# power_1_0.net
KiCad netlist of a schematic drawn in EAGLE
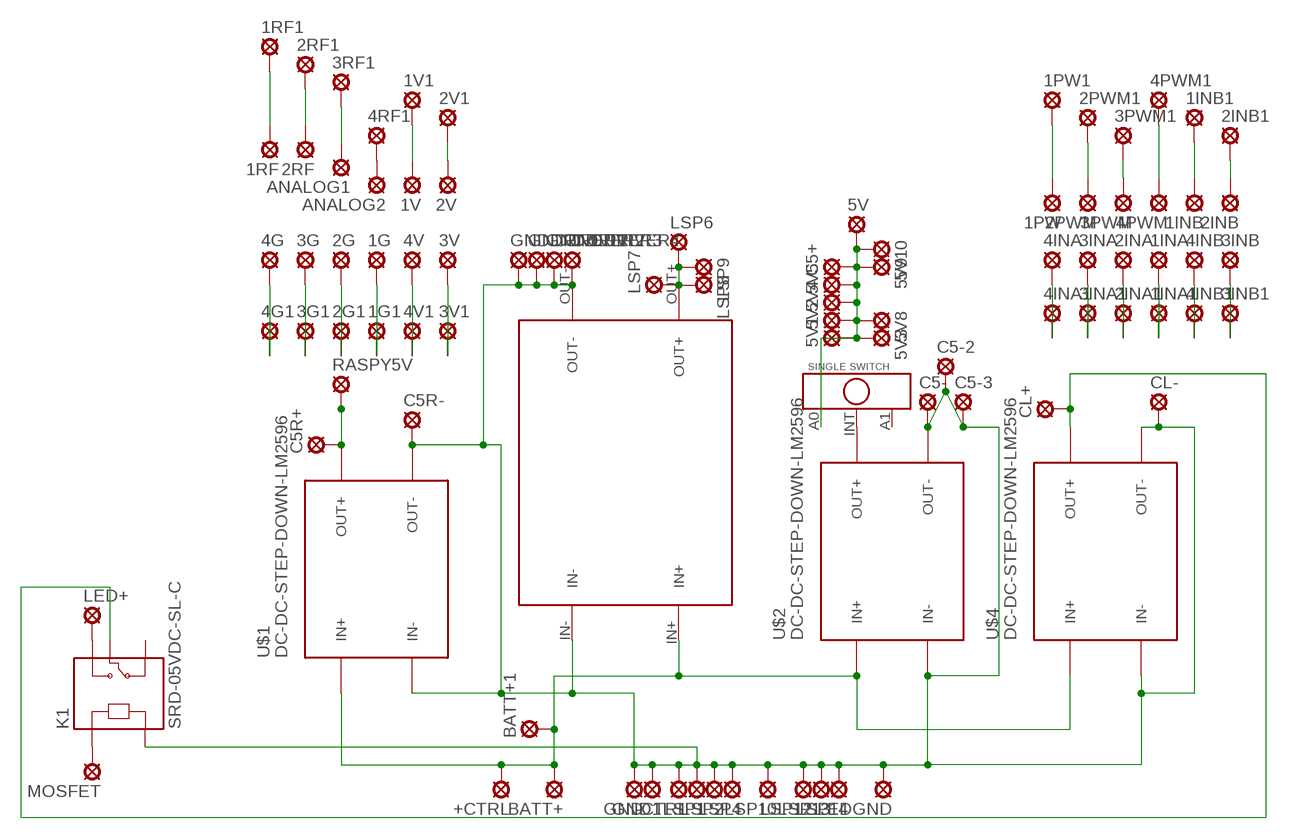
[diagram p0: schematic, sheet 1]

(export (version "E")
  (design (tool "Eeschema 10.0.6"))
  (components
    (comp (ref "+CTRL")
      (value "LSP10")
      (footprint "eagle-import:LSP10")
      (libsource (lib "eagle-import") (part "LSP10"))
    )
    (comp (ref "-CTRL")
      (value "LSP10")
      (footprint "eagle-import:LSP10")
      (libsource (lib "eagle-import") (part "LSP10"))
    )
    (comp (ref "1G")
      (value "LSP10")
      (footprint "eagle-import:LSP10")
      (libsource (lib "eagle-import") (part "LSP10"))
    )
    (comp (ref "1G1")
      (value "LSP10")
      (footprint "eagle-import:LSP10")
      (libsource (lib "eagle-import") (part "LSP10"))
    )
    (comp (ref "1INA")
      (value "LSP10")
      (footprint "eagle-import:LSP10")
      (libsource (lib "eagle-import") (part "LSP10"))
    )
    (comp (ref "1INA1")
      (value "LSP10")
      (footprint "eagle-import:LSP10")
      (libsource (lib "eagle-import") (part "LSP10"))
    )
    (comp (ref "1INB")
      (value "LSP10")
      (footprint "eagle-import:LSP10")
      (libsource (lib "eagle-import") (part "LSP10"))
    )
    (comp (ref "1INB1")
      (value "LSP10")
      (footprint "eagle-import:LSP10")
      (libsource (lib "eagle-import") (part "LSP10"))
    )
    (comp (ref "1PW")
      (value "LSP10")
      (footprint "eagle-import:LSP10")
      (libsource (lib "eagle-import") (part "LSP10"))
    )
    (comp (ref "1PW1")
      (value "LSP10")
      (footprint "eagle-import:LSP10")
      (libsource (lib "eagle-import") (part "LSP10"))
    )
    (comp (ref "1RF")
      (value "LSP10")
      (footprint "eagle-import:LSP10")
      (libsource (lib "eagle-import") (part "LSP10"))
    )
    (comp (ref "1RF1")
      (value "LSP10")
      (footprint "eagle-import:LSP10")
      (libsource (lib "eagle-import") (part "LSP10"))
    )
    (comp (ref "1V")
      (value "LSP10")
      (footprint "eagle-import:LSP10")
      (libsource (lib "eagle-import") (part "LSP10"))
    )
    (comp (ref "1V1")
      (value "LSP10")
      (footprint "eagle-import:LSP10")
      (libsource (lib "eagle-import") (part "LSP10"))
    )
    (comp (ref "2G")
      (value "LSP10")
      (footprint "eagle-import:LSP10")
      (libsource (lib "eagle-import") (part "LSP10"))
    )
    (comp (ref "2G1")
      (value "LSP10")
      (footprint "eagle-import:LSP10")
      (libsource (lib "eagle-import") (part "LSP10"))
    )
    (comp (ref "2INA")
      (value "LSP10")
      (footprint "eagle-import:LSP10")
      (libsource (lib "eagle-import") (part "LSP10"))
    )
    (comp (ref "2INA1")
      (value "LSP10")
      (footprint "eagle-import:LSP10")
      (libsource (lib "eagle-import") (part "LSP10"))
    )
    (comp (ref "2INB")
      (value "LSP10")
      (footprint "eagle-import:LSP10")
      (libsource (lib "eagle-import") (part "LSP10"))
    )
    (comp (ref "2INB1")
      (value "LSP10")
      (footprint "eagle-import:LSP10")
      (libsource (lib "eagle-import") (part "LSP10"))
    )
    (comp (ref "2PWM")
      (value "LSP10")
      (footprint "eagle-import:LSP10")
      (libsource (lib "eagle-import") (part "LSP10"))
    )
    (comp (ref "2PWM1")
      (value "LSP10")
      (footprint "eagle-import:LSP10")
      (libsource (lib "eagle-import") (part "LSP10"))
    )
    (comp (ref "2RF")
      (value "LSP10")
      (footprint "eagle-import:LSP10")
      (libsource (lib "eagle-import") (part "LSP10"))
    )
    (comp (ref "2RF1")
      (value "LSP10")
      (footprint "eagle-import:LSP10")
      (libsource (lib "eagle-import") (part "LSP10"))
    )
    (comp (ref "2V")
      (value "LSP10")
      (footprint "eagle-import:LSP10")
      (libsource (lib "eagle-import") (part "LSP10"))
    )
    (comp (ref "2V1")
      (value "LSP10")
      (footprint "eagle-import:LSP10")
      (libsource (lib "eagle-import") (part "LSP10"))
    )
    (comp (ref "3G")
      (value "LSP10")
      (footprint "eagle-import:LSP10")
      (libsource (lib "eagle-import") (part "LSP10"))
    )
    (comp (ref "3G1")
      (value "LSP10")
      (footprint "eagle-import:LSP10")
      (libsource (lib "eagle-import") (part "LSP10"))
    )
    (comp (ref "3INA")
      (value "LSP10")
      (footprint "eagle-import:LSP10")
      (libsource (lib "eagle-import") (part "LSP10"))
    )
    (comp (ref "3INA1")
      (value "LSP10")
      (footprint "eagle-import:LSP10")
      (libsource (lib "eagle-import") (part "LSP10"))
    )
    (comp (ref "3INB")
      (value "LSP10")
      (footprint "eagle-import:LSP10")
      (libsource (lib "eagle-import") (part "LSP10"))
    )
    (comp (ref "3INB1")
      (value "LSP10")
      (footprint "eagle-import:LSP10")
      (libsource (lib "eagle-import") (part "LSP10"))
    )
    (comp (ref "3PWM")
      (value "LSP10")
      (footprint "eagle-import:LSP10")
      (libsource (lib "eagle-import") (part "LSP10"))
    )
    (comp (ref "3PWM1")
      (value "LSP10")
      (footprint "eagle-import:LSP10")
      (libsource (lib "eagle-import") (part "LSP10"))
    )
    (comp (ref "3RF1")
      (value "LSP10")
      (footprint "eagle-import:LSP10")
      (libsource (lib "eagle-import") (part "LSP10"))
    )
    (comp (ref "3V")
      (value "LSP10")
      (footprint "eagle-import:LSP10")
      (libsource (lib "eagle-import") (part "LSP10"))
    )
    (comp (ref "3V1")
      (value "LSP10")
      (footprint "eagle-import:LSP10")
      (libsource (lib "eagle-import") (part "LSP10"))
    )
    (comp (ref "4G")
      (value "LSP10")
      (footprint "eagle-import:LSP10")
      (libsource (lib "eagle-import") (part "LSP10"))
    )
    (comp (ref "4G1")
      (value "LSP10")
      (footprint "eagle-import:LSP10")
      (libsource (lib "eagle-import") (part "LSP10"))
    )
    (comp (ref "4INA")
      (value "LSP10")
      (footprint "eagle-import:LSP10")
      (libsource (lib "eagle-import") (part "LSP10"))
    )
    (comp (ref "4INA1")
      (value "LSP10")
      (footprint "eagle-import:LSP10")
      (libsource (lib "eagle-import") (part "LSP10"))
    )
    (comp (ref "4INB")
      (value "LSP10")
      (footprint "eagle-import:LSP10")
      (libsource (lib "eagle-import") (part "LSP10"))
    )
    (comp (ref "4INB1")
      (value "LSP10")
      (footprint "eagle-import:LSP10")
      (libsource (lib "eagle-import") (part "LSP10"))
    )
    (comp (ref "4PWM")
      (value "LSP10")
      (footprint "eagle-import:LSP10")
      (libsource (lib "eagle-import") (part "LSP10"))
    )
    (comp (ref "4PWM1")
      (value "LSP10")
      (footprint "eagle-import:LSP10")
      (libsource (lib "eagle-import") (part "LSP10"))
    )
    (comp (ref "4RF1")
      (value "LSP10")
      (footprint "eagle-import:LSP10")
      (libsource (lib "eagle-import") (part "LSP10"))
    )
    (comp (ref "4V")
      (value "LSP10")
      (footprint "eagle-import:LSP10")
      (libsource (lib "eagle-import") (part "LSP10"))
    )
    (comp (ref "4V1")
      (value "LSP10")
      (footprint "eagle-import:LSP10")
      (libsource (lib "eagle-import") (part "LSP10"))
    )
    (comp (ref "5V")
      (value "LSP10")
      (footprint "eagle-import:LSP10")
      (libsource (lib "eagle-import") (part "LSP10"))
    )
    (comp (ref "5V1")
      (value "LSP10")
      (footprint "eagle-import:LSP10")
      (libsource (lib "eagle-import") (part "LSP10"))
    )
    (comp (ref "5V2")
      (value "LSP10")
      (footprint "eagle-import:LSP10")
      (libsource (lib "eagle-import") (part "LSP10"))
    )
    (comp (ref "5V3")
      (value "LSP10")
      (footprint "eagle-import:LSP10")
      (libsource (lib "eagle-import") (part "LSP10"))
    )
    (comp (ref "5V4")
      (value "LSP10")
      (footprint "eagle-import:LSP10")
      (libsource (lib "eagle-import") (part "LSP10"))
    )
    (comp (ref "5V5")
      (value "LSP10")
      (footprint "eagle-import:LSP10")
      (libsource (lib "eagle-import") (part "LSP10"))
    )
    (comp (ref "5V8")
      (value "LSP10")
      (footprint "eagle-import:LSP10")
      (libsource (lib "eagle-import") (part "LSP10"))
    )
    (comp (ref "5V9")
      (value "LSP10")
      (footprint "eagle-import:LSP10")
      (libsource (lib "eagle-import") (part "LSP10"))
    )
    (comp (ref "5V10")
      (value "LSP10")
      (footprint "eagle-import:LSP10")
      (libsource (lib "eagle-import") (part "LSP10"))
    )
    (comp (ref "ANALOG1")
      (value "LSP10")
      (footprint "eagle-import:LSP10")
      (libsource (lib "eagle-import") (part "LSP10"))
    )
    (comp (ref "ANALOG2")
      (value "LSP10")
      (footprint "eagle-import:LSP10")
      (libsource (lib "eagle-import") (part "LSP10"))
    )
    (comp (ref "BATT+")
      (value "SE14")
      (footprint "eagle-import:SE14")
      (libsource (lib "eagle-import") (part "SE14"))
    )
    (comp (ref "BATT+1")
      (value "SE14")
      (footprint "eagle-import:SE14")
      (libsource (lib "eagle-import") (part "SE14"))
    )
    (comp (ref "C5+")
      (value "LSP10")
      (footprint "eagle-import:LSP10")
      (libsource (lib "eagle-import") (part "LSP10"))
    )
    (comp (ref "C5-")
      (value "LSP10")
      (footprint "eagle-import:LSP10")
      (libsource (lib "eagle-import") (part "LSP10"))
    )
    (comp (ref "C5-2")
      (value "LSP10")
      (footprint "eagle-import:LSP10")
      (libsource (lib "eagle-import") (part "LSP10"))
    )
    (comp (ref "C5-3")
      (value "LSP10")
      (footprint "eagle-import:LSP10")
      (libsource (lib "eagle-import") (part "LSP10"))
    )
    (comp (ref "C5R+")
      (value "LSP10")
      (footprint "eagle-import:LSP10")
      (libsource (lib "eagle-import") (part "LSP10"))
    )
    (comp (ref "C5R-")
      (value "LSP10")
      (footprint "eagle-import:LSP10")
      (libsource (lib "eagle-import") (part "LSP10"))
    )
    (comp (ref "CL+")
      (value "LSP10")
      (footprint "eagle-import:LSP10")
      (libsource (lib "eagle-import") (part "LSP10"))
    )
    (comp (ref "CL-")
      (value "LSP10")
      (footprint "eagle-import:LSP10")
      (libsource (lib "eagle-import") (part "LSP10"))
    )
    (comp (ref "GND")
      (value "SE14")
      (footprint "eagle-import:SE14")
      (libsource (lib "eagle-import") (part "SE14"))
    )
    (comp (ref "GND1")
      (value "SE14")
      (footprint "eagle-import:SE14")
      (libsource (lib "eagle-import") (part "SE14"))
    )
    (comp (ref "GNDDRIVER1")
      (value "SE14")
      (footprint "eagle-import:SE14")
      (libsource (lib "eagle-import") (part "SE14"))
    )
    (comp (ref "GNDDRIVER2")
      (value "SE14")
      (footprint "eagle-import:SE14")
      (libsource (lib "eagle-import") (part "SE14"))
    )
    (comp (ref "GNDDRIVER3")
      (value "SE14")
      (footprint "eagle-import:SE14")
      (libsource (lib "eagle-import") (part "SE14"))
    )
    (comp (ref "GNDDRIVER4")
      (value "SE14")
      (footprint "eagle-import:SE14")
      (libsource (lib "eagle-import") (part "SE14"))
    )
    (comp (ref "K1")
      (value "SRD-05VDC-SL-C")
      (footprint "eagle-import:RELAY_SRD-05VDC-SL-C")
      (fields (field (name "MF") "Songle Relay"))
      (libsource (lib "eagle-import") (part "SRD-05VDC-SL-C"))
    )
    (comp (ref "LED+")
      (value "SE14")
      (footprint "eagle-import:SE14")
      (libsource (lib "eagle-import") (part "SE14"))
    )
    (comp (ref "LEDGND")
      (value "SE14")
      (footprint "eagle-import:SE14")
      (libsource (lib "eagle-import") (part "SE14"))
    )
    (comp (ref "LSP1")
      (value "LSP10")
      (footprint "eagle-import:LSP10")
      (libsource (lib "eagle-import") (part "LSP10"))
    )
    (comp (ref "LSP2")
      (value "LSP10")
      (footprint "eagle-import:LSP10")
      (libsource (lib "eagle-import") (part "LSP10"))
    )
    (comp (ref "LSP4")
      (value "LSP10")
      (footprint "eagle-import:LSP10")
      (libsource (lib "eagle-import") (part "LSP10"))
    )
    (comp (ref "LSP6")
      (value "SE14")
      (footprint "eagle-import:SE14")
      (libsource (lib "eagle-import") (part "SE14"))
    )
    (comp (ref "LSP7")
      (value "SE14")
      (footprint "eagle-import:SE14")
      (libsource (lib "eagle-import") (part "SE14"))
    )
    (comp (ref "LSP8")
      (value "SE14")
      (footprint "eagle-import:SE14")
      (libsource (lib "eagle-import") (part "SE14"))
    )
    (comp (ref "LSP9")
      (value "SE14")
      (footprint "eagle-import:SE14")
      (libsource (lib "eagle-import") (part "SE14"))
    )
    (comp (ref "LSP10")
      (value "LSP10")
      (footprint "eagle-import:LSP10")
      (libsource (lib "eagle-import") (part "LSP10"))
    )
    (comp (ref "LSP12")
      (value "LSP10")
      (footprint "eagle-import:LSP10")
      (libsource (lib "eagle-import") (part "LSP10"))
    )
    (comp (ref "LSP13")
      (value "LSP10")
      (footprint "eagle-import:LSP10")
      (libsource (lib "eagle-import") (part "LSP10"))
    )
    (comp (ref "LSP14")
      (value "LSP10")
      (footprint "eagle-import:LSP10")
      (libsource (lib "eagle-import") (part "LSP10"))
    )
    (comp (ref "MOSFET")
      (value "LSP10")
      (footprint "eagle-import:LSP10")
      (libsource (lib "eagle-import") (part "LSP10"))
    )
    (comp (ref "RASPY5V")
      (value "LSP10")
      (footprint "eagle-import:LSP10")
      (libsource (lib "eagle-import") (part "LSP10"))
    )
    (comp (ref "U$1")
      (value "DC-DC-STEP-DOWN-LM2596")
      (footprint "eagle-import:DC-DC-STEP-DOWN-LM2596")
      (libsource (lib "eagle-import") (part "DC-DC-STEP-DOWN-LM2596"))
    )
    (comp (ref "U$2")
      (value "DC-DC-STEP-DOWN-LM2596")
      (footprint "eagle-import:DC-DC-STEP-DOWN-LM2596")
      (libsource (lib "eagle-import") (part "DC-DC-STEP-DOWN-LM2596"))
    )
    (comp (ref "U$3")
      (value "DC-DCSTEPUP/DOWNBUCKCONVERTER")
      (footprint "eagle-import:DC-DCSTEPUP_DOWNBUCKCONVERTER")
      (libsource (lib "eagle-import") (part "DC-DCSTEPUP/DOWNBUCKCONVERTER"))
    )
    (comp (ref "U$4")
      (value "DC-DC-STEP-DOWN-LM2596")
      (footprint "eagle-import:DC-DC-STEP-DOWN-LM2596")
      (libsource (lib "eagle-import") (part "DC-DC-STEP-DOWN-LM2596"))
    )
    (comp (ref "U$5")
      (value "SINGE_SWITCH")
      (footprint "eagle-import:SINGLE_SWITCH")
      (libsource (lib "eagle-import") (part "SINGE_SWITCH"))
    )
  )
  (nets
    (net (code "1") (name "Net-(+CTRL-PadMP)") (class "Default")
      (node (ref "+CTRL") (pin "MP") (pinfunction "MP_MP") (pintype "passive"))
      (node (ref "BATT+") (pin "MP") (pinfunction "MP_MP") (pintype "passive"))
      (node (ref "BATT+1") (pin "MP") (pinfunction "MP_MP") (pintype "passive"))
      (node (ref "U$1") (pin "IN+") (pinfunction "IN+_IN+") (pintype "bidirectional"))
      (node (ref "U$2") (pin "IN+") (pinfunction "IN+_IN+") (pintype "bidirectional"))
      (node (ref "U$3") (pin "IN+") (pinfunction "IN+_IN+") (pintype "bidirectional"))
      (node (ref "U$4") (pin "IN+") (pinfunction "IN+_IN+") (pintype "bidirectional"))
    )
    (net (code "2") (name "Net-(-CTRL-PadMP)") (class "Default")
      (node (ref "-CTRL") (pin "MP") (pinfunction "MP_MP") (pintype "passive"))
      (node (ref "C5-") (pin "MP") (pinfunction "MP_MP") (pintype "passive"))
      (node (ref "C5-2") (pin "MP") (pinfunction "MP_MP") (pintype "passive"))
      (node (ref "C5-3") (pin "MP") (pinfunction "MP_MP") (pintype "passive"))
      (node (ref "C5R-") (pin "MP") (pinfunction "MP_MP") (pintype "passive"))
      (node (ref "CL-") (pin "MP") (pinfunction "MP_MP") (pintype "passive"))
      (node (ref "GND") (pin "MP") (pinfunction "MP_MP") (pintype "passive"))
      (node (ref "GND1") (pin "MP") (pinfunction "MP_MP") (pintype "passive"))
      (node (ref "GNDDRIVER1") (pin "MP") (pinfunction "MP_MP") (pintype "passive"))
      (node (ref "GNDDRIVER2") (pin "MP") (pinfunction "MP_MP") (pintype "passive"))
      (node (ref "GNDDRIVER3") (pin "MP") (pinfunction "MP_MP") (pintype "passive"))
      (node (ref "GNDDRIVER4") (pin "MP") (pinfunction "MP_MP") (pintype "passive"))
      (node (ref "K1") (pin "A2") (pinfunction "A2_A2") (pintype "passive"))
      (node (ref "LEDGND") (pin "MP") (pinfunction "MP_MP") (pintype "passive"))
      (node (ref "LSP1") (pin "MP") (pinfunction "MP_MP") (pintype "passive"))
      (node (ref "LSP10") (pin "MP") (pinfunction "MP_MP") (pintype "passive"))
      (node (ref "LSP12") (pin "MP") (pinfunction "MP_MP") (pintype "passive"))
      (node (ref "LSP13") (pin "MP") (pinfunction "MP_MP") (pintype "passive"))
      (node (ref "LSP14") (pin "MP") (pinfunction "MP_MP") (pintype "passive"))
      (node (ref "LSP2") (pin "MP") (pinfunction "MP_MP") (pintype "passive"))
      (node (ref "LSP4") (pin "MP") (pinfunction "MP_MP") (pintype "passive"))
      (node (ref "U$1") (pin "IN-") (pinfunction "IN-_IN-") (pintype "bidirectional"))
      (node (ref "U$1") (pin "OUT-") (pinfunction "OUT-_OUT-") (pintype "bidirectional"))
      (node (ref "U$2") (pin "IN-") (pinfunction "IN-_IN-") (pintype "bidirectional"))
      (node (ref "U$2") (pin "OUT-") (pinfunction "OUT-_OUT-") (pintype "bidirectional"))
      (node (ref "U$3") (pin "IN-") (pinfunction "IN-_IN-") (pintype "bidirectional"))
      (node (ref "U$3") (pin "OUT-") (pinfunction "OUT-_OUT-") (pintype "bidirectional"))
      (node (ref "U$4") (pin "IN-") (pinfunction "IN-_IN-") (pintype "bidirectional"))
      (node (ref "U$4") (pin "OUT-") (pinfunction "OUT-_OUT-") (pintype "bidirectional"))
    )
    (net (code "3") (name "Net-(1G-PadMP)") (class "Default")
      (node (ref "1G") (pin "MP") (pinfunction "MP_MP") (pintype "passive"))
      (node (ref "1G1") (pin "MP") (pinfunction "MP_MP") (pintype "passive"))
    )
    (net (code "4") (name "Net-(1INA-PadMP)") (class "Default")
      (node (ref "1INA") (pin "MP") (pinfunction "MP_MP") (pintype "passive"))
      (node (ref "1INA1") (pin "MP") (pinfunction "MP_MP") (pintype "passive"))
    )
    (net (code "5") (name "Net-(1INB-PadMP)") (class "Default")
      (node (ref "1INB") (pin "MP") (pinfunction "MP_MP") (pintype "passive"))
      (node (ref "1INB1") (pin "MP") (pinfunction "MP_MP") (pintype "passive"))
    )
    (net (code "6") (name "Net-(1PW-PadMP)") (class "Default")
      (node (ref "1PW") (pin "MP") (pinfunction "MP_MP") (pintype "passive"))
      (node (ref "1PW1") (pin "MP") (pinfunction "MP_MP") (pintype "passive"))
    )
    (net (code "7") (name "Net-(1RF-PadMP)") (class "Default")
      (node (ref "1RF") (pin "MP") (pinfunction "MP_MP") (pintype "passive"))
      (node (ref "1RF1") (pin "MP") (pinfunction "MP_MP") (pintype "passive"))
    )
    (net (code "8") (name "Net-(1V-PadMP)") (class "Default")
      (node (ref "1V") (pin "MP") (pinfunction "MP_MP") (pintype "passive"))
      (node (ref "1V1") (pin "MP") (pinfunction "MP_MP") (pintype "passive"))
    )
    (net (code "9") (name "Net-(2G-PadMP)") (class "Default")
      (node (ref "2G") (pin "MP") (pinfunction "MP_MP") (pintype "passive"))
      (node (ref "2G1") (pin "MP") (pinfunction "MP_MP") (pintype "passive"))
    )
    (net (code "10") (name "Net-(2INA-PadMP)") (class "Default")
      (node (ref "2INA") (pin "MP") (pinfunction "MP_MP") (pintype "passive"))
      (node (ref "2INA1") (pin "MP") (pinfunction "MP_MP") (pintype "passive"))
    )
    (net (code "11") (name "Net-(2INB-PadMP)") (class "Default")
      (node (ref "2INB") (pin "MP") (pinfunction "MP_MP") (pintype "passive"))
      (node (ref "2INB1") (pin "MP") (pinfunction "MP_MP") (pintype "passive"))
    )
    (net (code "12") (name "Net-(2PWM-PadMP)") (class "Default")
      (node (ref "2PWM") (pin "MP") (pinfunction "MP_MP") (pintype "passive"))
      (node (ref "2PWM1") (pin "MP") (pinfunction "MP_MP") (pintype "passive"))
    )
    (net (code "13") (name "Net-(2RF-PadMP)") (class "Default")
      (node (ref "2RF") (pin "MP") (pinfunction "MP_MP") (pintype "passive"))
      (node (ref "2RF1") (pin "MP") (pinfunction "MP_MP") (pintype "passive"))
    )
    (net (code "14") (name "Net-(2V-PadMP)") (class "Default")
      (node (ref "2V") (pin "MP") (pinfunction "MP_MP") (pintype "passive"))
      (node (ref "2V1") (pin "MP") (pinfunction "MP_MP") (pintype "passive"))
    )
    (net (code "15") (name "Net-(3G-PadMP)") (class "Default")
      (node (ref "3G") (pin "MP") (pinfunction "MP_MP") (pintype "passive"))
      (node (ref "3G1") (pin "MP") (pinfunction "MP_MP") (pintype "passive"))
    )
    (net (code "16") (name "Net-(3INA-PadMP)") (class "Default")
      (node (ref "3INA") (pin "MP") (pinfunction "MP_MP") (pintype "passive"))
      (node (ref "3INA1") (pin "MP") (pinfunction "MP_MP") (pintype "passive"))
    )
    (net (code "17") (name "Net-(3INB-PadMP)") (class "Default")
      (node (ref "3INB") (pin "MP") (pinfunction "MP_MP") (pintype "passive"))
      (node (ref "3INB1") (pin "MP") (pinfunction "MP_MP") (pintype "passive"))
    )
    (net (code "18") (name "Net-(3PWM-PadMP)") (class "Default")
      (node (ref "3PWM") (pin "MP") (pinfunction "MP_MP") (pintype "passive"))
      (node (ref "3PWM1") (pin "MP") (pinfunction "MP_MP") (pintype "passive"))
    )
    (net (code "19") (name "Net-(3RF1-PadMP)") (class "Default")
      (node (ref "3RF1") (pin "MP") (pinfunction "MP_MP") (pintype "passive"))
      (node (ref "ANALOG1") (pin "MP") (pinfunction "MP_MP") (pintype "passive"))
    )
    (net (code "20") (name "Net-(3V-PadMP)") (class "Default")
      (node (ref "3V") (pin "MP") (pinfunction "MP_MP") (pintype "passive"))
      (node (ref "3V1") (pin "MP") (pinfunction "MP_MP") (pintype "passive"))
    )
    (net (code "21") (name "Net-(4G-PadMP)") (class "Default")
      (node (ref "4G") (pin "MP") (pinfunction "MP_MP") (pintype "passive"))
      (node (ref "4G1") (pin "MP") (pinfunction "MP_MP") (pintype "passive"))
    )
    (net (code "22") (name "Net-(4INA-PadMP)") (class "Default")
      (node (ref "4INA") (pin "MP") (pinfunction "MP_MP") (pintype "passive"))
      (node (ref "4INA1") (pin "MP") (pinfunction "MP_MP") (pintype "passive"))
    )
    (net (code "23") (name "Net-(4INB-PadMP)") (class "Default")
      (node (ref "4INB") (pin "MP") (pinfunction "MP_MP") (pintype "passive"))
      (node (ref "4INB1") (pin "MP") (pinfunction "MP_MP") (pintype "passive"))
    )
    (net (code "24") (name "Net-(4PWM-PadMP)") (class "Default")
      (node (ref "4PWM") (pin "MP") (pinfunction "MP_MP") (pintype "passive"))
      (node (ref "4PWM1") (pin "MP") (pinfunction "MP_MP") (pintype "passive"))
    )
    (net (code "25") (name "Net-(4RF1-PadMP)") (class "Default")
      (node (ref "4RF1") (pin "MP") (pinfunction "MP_MP") (pintype "passive"))
      (node (ref "ANALOG2") (pin "MP") (pinfunction "MP_MP") (pintype "passive"))
    )
    (net (code "26") (name "Net-(4V-PadMP)") (class "Default")
      (node (ref "4V") (pin "MP") (pinfunction "MP_MP") (pintype "passive"))
      (node (ref "4V1") (pin "MP") (pinfunction "MP_MP") (pintype "passive"))
    )
    (net (code "27") (name "Net-(5V-PadMP)") (class "Default")
      (node (ref "5V") (pin "MP") (pinfunction "MP_MP") (pintype "passive"))
      (node (ref "5V1") (pin "MP") (pinfunction "MP_MP") (pintype "passive"))
      (node (ref "5V10") (pin "MP") (pinfunction "MP_MP") (pintype "passive"))
      (node (ref "5V2") (pin "MP") (pinfunction "MP_MP") (pintype "passive"))
      (node (ref "5V3") (pin "MP") (pinfunction "MP_MP") (pintype "passive"))
      (node (ref "5V4") (pin "MP") (pinfunction "MP_MP") (pintype "passive"))
      (node (ref "5V5") (pin "MP") (pinfunction "MP_MP") (pintype "passive"))
      (node (ref "5V8") (pin "MP") (pinfunction "MP_MP") (pintype "passive"))
      (node (ref "5V9") (pin "MP") (pinfunction "MP_MP") (pintype "passive"))
      (node (ref "C5+") (pin "MP") (pinfunction "MP_MP") (pintype "passive"))
      (node (ref "U$5") (pin "A0") (pinfunction "A0_A0") (pintype "bidirectional"))
    )
    (net (code "28") (name "Net-(C5R+-PadMP)") (class "Default")
      (node (ref "C5R+") (pin "MP") (pinfunction "MP_MP") (pintype "passive"))
      (node (ref "RASPY5V") (pin "MP") (pinfunction "MP_MP") (pintype "passive"))
      (node (ref "U$1") (pin "OUT+") (pinfunction "OUT+_OUT+") (pintype "bidirectional"))
    )
    (net (code "29") (name "Net-(CL+-PadMP)") (class "Default")
      (node (ref "CL+") (pin "MP") (pinfunction "MP_MP") (pintype "passive"))
      (node (ref "K1") (pin "COM") (pinfunction "COM_COM") (pintype "passive"))
      (node (ref "U$4") (pin "OUT+") (pinfunction "OUT+_OUT+") (pintype "bidirectional"))
    )
    (net (code "30") (name "Net-(K1-PadA1)") (class "Default")
      (node (ref "K1") (pin "A1") (pinfunction "A1_A1") (pintype "passive"))
      (node (ref "MOSFET") (pin "MP") (pinfunction "MP_MP") (pintype "passive"))
    )
    (net (code "31") (name "Net-(K1-PadNO)") (class "Default")
      (node (ref "K1") (pin "NO") (pinfunction "NO_NO") (pintype "passive"))
      (node (ref "LED+") (pin "MP") (pinfunction "MP_MP") (pintype "passive"))
    )
    (net (code "32") (name "Net-(LSP6-PadMP)") (class "Default")
      (node (ref "LSP6") (pin "MP") (pinfunction "MP_MP") (pintype "passive"))
      (node (ref "LSP7") (pin "MP") (pinfunction "MP_MP") (pintype "passive"))
      (node (ref "LSP8") (pin "MP") (pinfunction "MP_MP") (pintype "passive"))
      (node (ref "LSP9") (pin "MP") (pinfunction "MP_MP") (pintype "passive"))
      (node (ref "U$3") (pin "OUT+") (pinfunction "OUT+_OUT+") (pintype "bidirectional"))
    )
    (net (code "33") (name "Net-(U$2-PadOUT+)") (class "Default")
      (node (ref "U$2") (pin "OUT+") (pinfunction "OUT+_OUT+") (pintype "bidirectional"))
      (node (ref "U$5") (pin "INT") (pinfunction "INT_INT") (pintype "bidirectional"))
    )
    (net (code "34") (name "unconnected-(K1-PadNC)") (class "Default")
      (node (ref "K1") (pin "NC") (pinfunction "NC_NC") (pintype "passive"))
    )
    (net (code "35") (name "unconnected-(U$5-PadA1)") (class "Default")
      (node (ref "U$5") (pin "A1") (pinfunction "A1_A1") (pintype "bidirectional"))
    )
  )
)
